# Schematic_Devices.net
KiCad netlist of a schematic drawn in Altium Designer
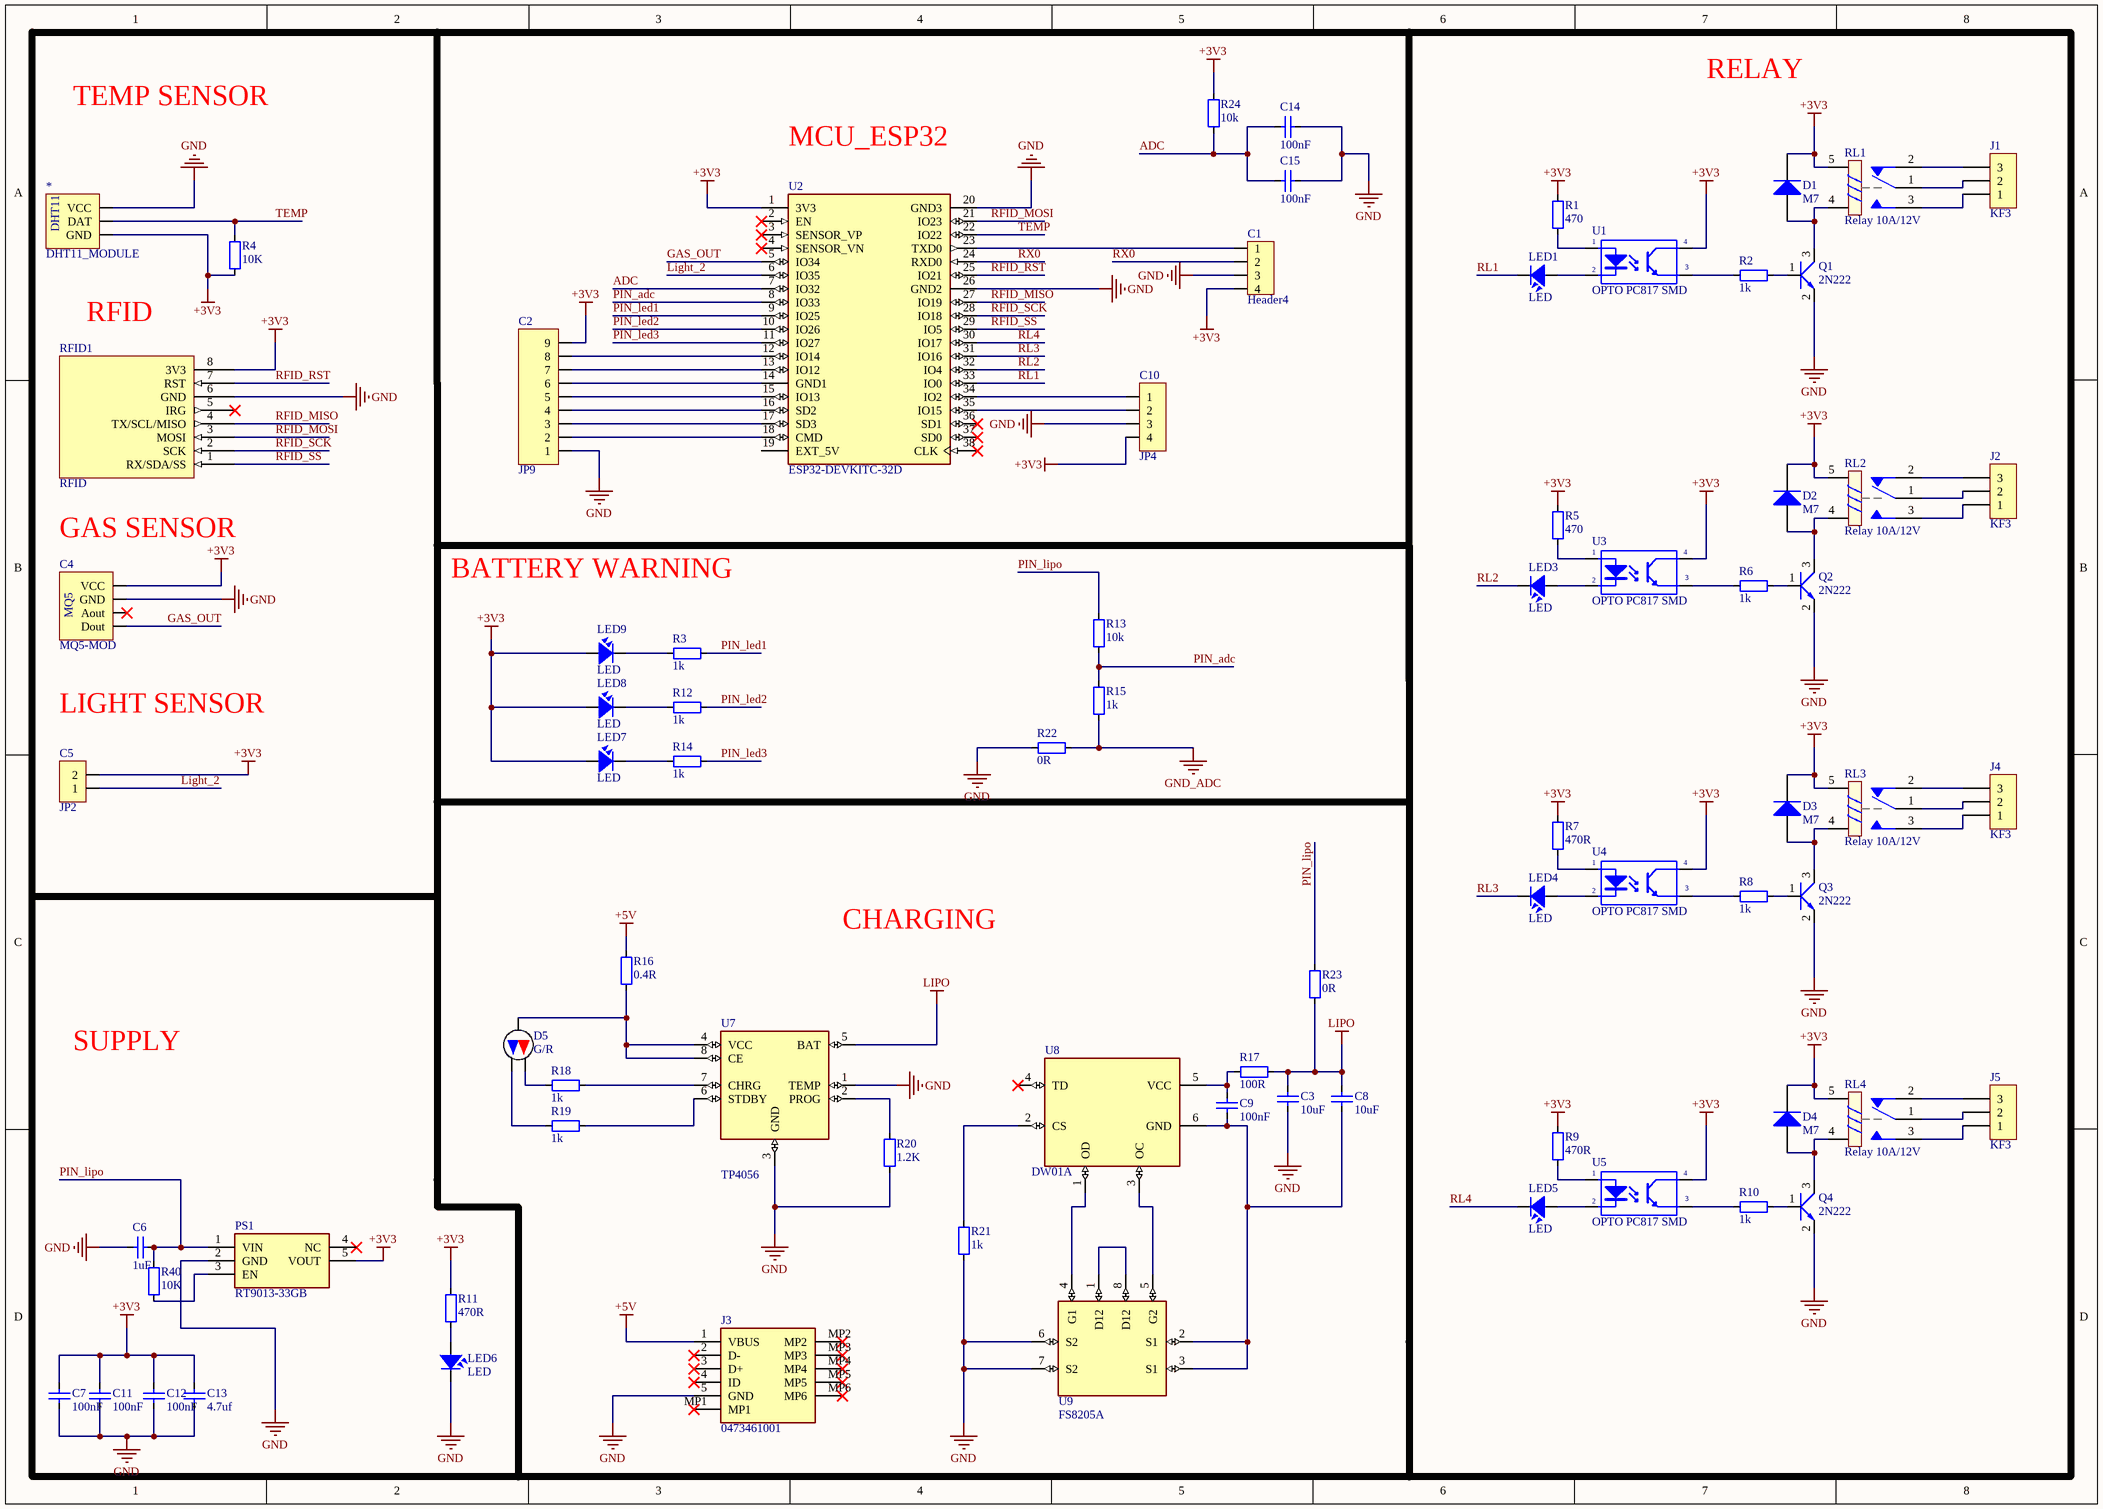
[diagram p0: Schematic_Devices.SchDoc]

(export (version "E")
  (design (tool "Eeschema 10.0.6"))
  (components
    (comp (ref "*")
      (value "DHT11_MODULE")
      (footprint "DHT11_MODULE")
      (libsource (lib "My Library") (part "DHT11_MODULE"))
    )
    (comp (ref "C1")
      (value "Header4")
      (footprint "HDR4")
      (description "Header IDC, 4 x 1 Pin Vertical 2.54mm Pitch (Non-Boxed, Male)")
      (fields
        (field (name "MANUFACTURER") "Würth Elektronik eiSos GmbH")
        (field (name "PARTNO") "613002143121")
        (field (name "CREATED BY") "Karrer Zheng")
      )
      (libsource (lib "My Library") (part "Header4"))
    )
    (comp (ref "C2")
      (value "JP9")
      (footprint "JP9-C1T")
      (description "WR-PHD 2.54 mm Angled Socket Header")
      (fields
        (field (name "MANUFACTURER") "Würth Elektronik eiSos GmbH")
        (field (name "PARTNO") "613009143121")
        (field (name "CREATED BY") "Karrer Zheng")
      )
      (libsource (lib "My Library") (part "JP9"))
    )
    (comp (ref "C3")
      (value "10uF")
      (footprint "CAP_0805")
      (description "Capacitor")
      (fields (field (name "PUBLISHER") "Altium Limited"))
      (libsource (lib "My Library") (part "CapSMD"))
    )
    (comp (ref "C4")
      (value "MQ5-MOD")
      (footprint "JP4-C1T")
      (fields
        (field (name "MANUFACTURER") "Würth Elektronik eiSos GmbH")
        (field (name "PARTNO") "613004143121")
        (field (name "CREATED BY") "Karrer Zheng")
      )
      (libsource (lib "My Library") (part "MQ5-MOD"))
    )
    (comp (ref "C5")
      (value "JP2")
      (footprint "JP2-C1T")
      (description "WR-PHD 2.54 mm Angled Socket Header")
      (fields
        (field (name "MANUFACTURER") "Würth Elektronik eiSos GmbH")
        (field (name "PARTNO") "613002143121")
        (field (name "CREATED BY") "Karrer Zheng")
      )
      (libsource (lib "My Library") (part "JP2"))
    )
    (comp (ref "C6")
      (value "1uF")
      (footprint "CAP_0805")
      (description "Capacitor")
      (fields (field (name "PUBLISHER") "Altium Limited"))
      (libsource (lib "My Library") (part "CapSMD"))
    )
    (comp (ref "C7")
      (value "100nF")
      (footprint "CAP_0805")
      (description "Capacitor")
      (fields (field (name "PUBLISHER") "Altium Limited"))
      (libsource (lib "My Library") (part "CapSMD"))
    )
    (comp (ref "C8")
      (value "10uF")
      (footprint "CAP_0805")
      (description "Capacitor")
      (fields (field (name "PUBLISHER") "Altium Limited"))
      (libsource (lib "My Library") (part "CapSMD"))
    )
    (comp (ref "C9")
      (value "100nF")
      (footprint "CAP_0805")
      (description "Capacitor")
      (fields (field (name "PUBLISHER") "Altium Limited"))
      (libsource (lib "My Library") (part "CapSMD"))
    )
    (comp (ref "C10")
      (value "JP4")
      (footprint "JP4-C1T")
      (description "WR-PHD 2.54 mm Angled Socket Header")
      (fields
        (field (name "MANUFACTURER") "Würth Elektronik eiSos GmbH")
        (field (name "PARTNO") "613004143121")
        (field (name "CREATED BY") "Karrer Zheng")
      )
      (libsource (lib "My Library") (part "JP4"))
    )
    (comp (ref "C11")
      (value "100nF")
      (footprint "CAP_0805")
      (description "Capacitor")
      (fields (field (name "PUBLISHER") "Altium Limited"))
      (libsource (lib "My Library") (part "CapSMD"))
    )
    (comp (ref "C12")
      (value "100nF")
      (footprint "CAP_0805")
      (description "Capacitor")
      (fields (field (name "PUBLISHER") "Altium Limited"))
      (libsource (lib "My Library") (part "CapSMD"))
    )
    (comp (ref "C13")
      (value "4.7uf")
      (footprint "CAP_0805")
      (description "Capacitor")
      (fields (field (name "PUBLISHER") "Altium Limited"))
      (libsource (lib "My Library") (part "CapSMD"))
    )
    (comp (ref "C14")
      (value "100nF")
      (footprint "CAP_0805")
      (description "Capacitor")
      (fields (field (name "PUBLISHER") "Altium Limited"))
      (libsource (lib "My Library") (part "CapSMD"))
    )
    (comp (ref "C15")
      (value "100nF")
      (footprint "CAP_0805")
      (description "Capacitor")
      (fields (field (name "PUBLISHER") "Altium Limited"))
      (libsource (lib "My Library") (part "CapSMD"))
    )
    (comp (ref "D1")
      (value "M7")
      (footprint "DO-214AC(SMA)")
      (description "Dán")
      (libsource (lib "Altium_Lib_by_KhueNguyenCreator") (part "Diode M7 ( 4007 )"))
    )
    (comp (ref "D2")
      (value "M7")
      (footprint "DO-214AC(SMA)")
      (description "Dán")
      (libsource (lib "Altium_Lib_by_KhueNguyenCreator") (part "Diode M7 ( 4007 )"))
    )
    (comp (ref "D3")
      (value "M7")
      (footprint "DO-214AC(SMA)")
      (description "Dán")
      (libsource (lib "Altium_Lib_by_KhueNguyenCreator") (part "Diode M7 ( 4007 )"))
    )
    (comp (ref "D4")
      (value "M7")
      (footprint "DO-214AC(SMA)")
      (description "Dán")
      (libsource (lib "Altium_Lib_by_KhueNguyenCreator") (part "Diode M7 ( 4007 )"))
    )
    (comp (ref "D5")
      (value "G/R")
      (footprint "LED_3MM_DUAL RA")
      (description "LED BLUE/RED DIFFUSED T-1 T/H 3MM")
      (fields (field (name "MFR") "SunLED") (field (name "MPN") "XLMDKCBD34M"))
      (libsource (lib "BYTECH_HW_LIB_2019 (1)") (part "LED_3MM_RA"))
    )
    (comp (ref "J1")
      (value "KF3")
      (footprint "KF3-5.08")
      (fields
        (field (name "MANUFACTURER") "Würth Elektronik eiSos GmbH")
        (field (name "PARTNO") "691103110003")
        (field (name "CREATED BY") "Karrer Zheng")
      )
      (libsource (lib "My Library") (part "KF3"))
    )
    (comp (ref "J2")
      (value "KF3")
      (footprint "KF3-5.08")
      (fields
        (field (name "MANUFACTURER") "Würth Elektronik eiSos GmbH")
        (field (name "PARTNO") "691103110003")
        (field (name "CREATED BY") "Karrer Zheng")
      )
      (libsource (lib "My Library") (part "KF3"))
    )
    (comp (ref "J3")
      (value "0473461001")
      (footprint "USB-M1")
      (description "Connector")
      (libsource (lib "*") (part "0473461001"))
    )
    (comp (ref "J4")
      (value "KF3")
      (footprint "KF3-5.08")
      (fields
        (field (name "MANUFACTURER") "Würth Elektronik eiSos GmbH")
        (field (name "PARTNO") "691103110003")
        (field (name "CREATED BY") "Karrer Zheng")
      )
      (libsource (lib "My Library") (part "KF3"))
    )
    (comp (ref "J5")
      (value "KF3")
      (footprint "KF3-5.08")
      (fields
        (field (name "MANUFACTURER") "Würth Elektronik eiSos GmbH")
        (field (name "PARTNO") "691103110003")
        (field (name "CREATED BY") "Karrer Zheng")
      )
      (libsource (lib "My Library") (part "KF3"))
    )
    (comp (ref "LED1")
      (value "LED")
      (footprint "LED-0805-Red")
      (description "LED Single colour Green and Red")
      (libsource (lib "My Library") (part "LED"))
    )
    (comp (ref "LED3")
      (value "LED")
      (footprint "LED-0805-Red")
      (description "LED Single colour Green and Red")
      (libsource (lib "My Library") (part "LED"))
    )
    (comp (ref "LED4")
      (value "LED")
      (footprint "LED-0805-Red")
      (description "LED Single colour Green and Red")
      (libsource (lib "My Library") (part "LED"))
    )
    (comp (ref "LED5")
      (value "LED")
      (footprint "LED-0805-Red")
      (description "LED Single colour Green and Red")
      (libsource (lib "My Library") (part "LED"))
    )
    (comp (ref "LED6")
      (value "LED")
      (footprint "LED-0805-Blue")
      (description "LED Single colour Green and Red")
      (libsource (lib "My Library") (part "LED"))
    )
    (comp (ref "LED7")
      (value "LED")
      (footprint "LED-0805-Orange")
      (description "LED Single colour Green and Red")
      (libsource (lib "My Library") (part "LED"))
    )
    (comp (ref "LED8")
      (value "LED")
      (footprint "LED-0805-Orange")
      (description "LED Single colour Green and Red")
      (libsource (lib "My Library") (part "LED"))
    )
    (comp (ref "LED9")
      (value "LED")
      (footprint "LED-0805-Blue")
      (description "LED Single colour Green and Red")
      (libsource (lib "My Library") (part "LED"))
    )
    (comp (ref "PS1")
      (value "RT9013-33GB")
      (footprint "SamacSys:SOT94P279X130-5N")
      (description "Power Supply")
      (libsource (lib "*") (part "RT9013-33GB"))
    )
    (comp (ref "Q1")
      (value "2N222")
      (footprint "SOT23D")
      (description "NPN 600mW, ECB")
      (libsource (lib "My Library") (part "2N222"))
    )
    (comp (ref "Q2")
      (value "2N222")
      (footprint "SOT23D")
      (description "NPN 600mW, ECB")
      (libsource (lib "My Library") (part "2N222"))
    )
    (comp (ref "Q3")
      (value "2N222")
      (footprint "SOT23D")
      (description "NPN 600mW, ECB")
      (libsource (lib "My Library") (part "2N222"))
    )
    (comp (ref "Q4")
      (value "2N222")
      (footprint "SOT23D")
      (description "NPN 600mW, ECB")
      (libsource (lib "My Library") (part "2N222"))
    )
    (comp (ref "R1")
      (value "470")
      (footprint "RES-SMD-0805")
      (description "Resistor")
      (fields
        (field (name "MANUFACTURER") "Generic Components")
        (field (name "PUBLISHER") "Altium Hobart Technology Centre")
      )
      (libsource (lib "My Library") (part "Resistor - SMD"))
    )
    (comp (ref "R2")
      (value "1k")
      (footprint "RES-SMD-0805")
      (description "Resistor")
      (fields
        (field (name "MANUFACTURER") "Generic Components")
        (field (name "PUBLISHER") "Altium Hobart Technology Centre")
      )
      (libsource (lib "My Library") (part "Resistor - SMD"))
    )
    (comp (ref "R3")
      (value "1k")
      (footprint "RES-SMD-0805")
      (description "Resistor")
      (fields
        (field (name "MANUFACTURER") "Generic Components")
        (field (name "PUBLISHER") "Altium Hobart Technology Centre")
      )
      (libsource (lib "My Library") (part "Resistor - SMD"))
    )
    (comp (ref "R4")
      (value "10K")
      (footprint "RES-SMD-0805")
      (description "Resistor")
      (fields
        (field (name "MANUFACTURER") "Generic Components")
        (field (name "PUBLISHER") "Altium Hobart Technology Centre")
      )
      (libsource (lib "My Library") (part "Resistor - SMD"))
    )
    (comp (ref "R5")
      (value "470")
      (footprint "RES-SMD-0805")
      (description "Resistor")
      (fields
        (field (name "MANUFACTURER") "Generic Components")
        (field (name "PUBLISHER") "Altium Hobart Technology Centre")
      )
      (libsource (lib "My Library") (part "Resistor - SMD"))
    )
    (comp (ref "R6")
      (value "1k")
      (footprint "RES-SMD-0805")
      (description "Resistor")
      (fields
        (field (name "MANUFACTURER") "Generic Components")
        (field (name "PUBLISHER") "Altium Hobart Technology Centre")
      )
      (libsource (lib "My Library") (part "Resistor - SMD"))
    )
    (comp (ref "R7")
      (value "470R")
      (footprint "RES-SMD-0805")
      (description "Resistor")
      (fields
        (field (name "MANUFACTURER") "Generic Components")
        (field (name "PUBLISHER") "Altium Hobart Technology Centre")
      )
      (libsource (lib "My Library") (part "Resistor - SMD"))
    )
    (comp (ref "R8")
      (value "1k")
      (footprint "RES-SMD-0805")
      (description "Resistor")
      (fields
        (field (name "MANUFACTURER") "Generic Components")
        (field (name "PUBLISHER") "Altium Hobart Technology Centre")
      )
      (libsource (lib "My Library") (part "Resistor - SMD"))
    )
    (comp (ref "R9")
      (value "470R")
      (footprint "RES-SMD-0805")
      (description "Resistor")
      (fields
        (field (name "MANUFACTURER") "Generic Components")
        (field (name "PUBLISHER") "Altium Hobart Technology Centre")
      )
      (libsource (lib "My Library") (part "Resistor - SMD"))
    )
    (comp (ref "R10")
      (value "1k")
      (footprint "RES-SMD-0805")
      (description "Resistor")
      (fields
        (field (name "MANUFACTURER") "Generic Components")
        (field (name "PUBLISHER") "Altium Hobart Technology Centre")
      )
      (libsource (lib "My Library") (part "Resistor - SMD"))
    )
    (comp (ref "R11")
      (value "470R")
      (footprint "RES-SMD-0805")
      (description "Resistor")
      (fields
        (field (name "MANUFACTURER") "Generic Components")
        (field (name "PUBLISHER") "Altium Hobart Technology Centre")
      )
      (libsource (lib "My Library") (part "Resistor - SMD"))
    )
    (comp (ref "R12")
      (value "1k")
      (footprint "RES-SMD-0805")
      (description "Resistor")
      (fields
        (field (name "MANUFACTURER") "Generic Components")
        (field (name "PUBLISHER") "Altium Hobart Technology Centre")
      )
      (libsource (lib "My Library") (part "Resistor - SMD"))
    )
    (comp (ref "R13")
      (value "10k")
      (footprint "RES-SMD-0805")
      (description "Resistor")
      (fields
        (field (name "MANUFACTURER") "Generic Components")
        (field (name "PUBLISHER") "Altium Hobart Technology Centre")
      )
      (libsource (lib "My Library") (part "Resistor - SMD"))
    )
    (comp (ref "R14")
      (value "1k")
      (footprint "RES-SMD-0805")
      (description "Resistor")
      (fields
        (field (name "MANUFACTURER") "Generic Components")
        (field (name "PUBLISHER") "Altium Hobart Technology Centre")
      )
      (libsource (lib "My Library") (part "Resistor - SMD"))
    )
    (comp (ref "R15")
      (value "1k")
      (footprint "RES-SMD-0805")
      (description "Resistor")
      (fields
        (field (name "MANUFACTURER") "Generic Components")
        (field (name "PUBLISHER") "Altium Hobart Technology Centre")
      )
      (libsource (lib "My Library") (part "Resistor - SMD"))
    )
    (comp (ref "R16")
      (value "0.4R")
      (footprint "RES-SMD-0805")
      (description "Resistor")
      (fields
        (field (name "MANUFACTURER") "Generic Components")
        (field (name "PUBLISHER") "Altium Hobart Technology Centre")
      )
      (libsource (lib "My Library") (part "Resistor - SMD"))
    )
    (comp (ref "R17")
      (value "100R")
      (footprint "RES-SMD-0805")
      (description "Resistor")
      (fields
        (field (name "MANUFACTURER") "Generic Components")
        (field (name "PUBLISHER") "Altium Hobart Technology Centre")
      )
      (libsource (lib "My Library") (part "Resistor - SMD"))
    )
    (comp (ref "R18")
      (value "1k")
      (footprint "RES-SMD-0805")
      (description "Resistor")
      (fields
        (field (name "MANUFACTURER") "Generic Components")
        (field (name "PUBLISHER") "Altium Hobart Technology Centre")
      )
      (libsource (lib "My Library") (part "Resistor - SMD"))
    )
    (comp (ref "R19")
      (value "1k")
      (footprint "RES-SMD-0805")
      (description "Resistor")
      (fields
        (field (name "MANUFACTURER") "Generic Components")
        (field (name "PUBLISHER") "Altium Hobart Technology Centre")
      )
      (libsource (lib "My Library") (part "Resistor - SMD"))
    )
    (comp (ref "R20")
      (value "1.2K")
      (footprint "RES-SMD-0805")
      (description "Resistor")
      (fields
        (field (name "MANUFACTURER") "Generic Components")
        (field (name "PUBLISHER") "Altium Hobart Technology Centre")
      )
      (libsource (lib "My Library") (part "Resistor - SMD"))
    )
    (comp (ref "R21")
      (value "1k")
      (footprint "RES-SMD-0805")
      (description "Resistor")
      (fields
        (field (name "MANUFACTURER") "Generic Components")
        (field (name "PUBLISHER") "Altium Hobart Technology Centre")
      )
      (libsource (lib "My Library") (part "Resistor - SMD"))
    )
    (comp (ref "R22")
      (value "0R")
      (footprint "RES-SMD-0805")
      (description "Resistor")
      (fields
        (field (name "MANUFACTURER") "Generic Components")
        (field (name "PUBLISHER") "Altium Hobart Technology Centre")
      )
      (libsource (lib "My Library") (part "Resistor - SMD"))
    )
    (comp (ref "R23")
      (value "0R")
      (footprint "RES-SMD-0805")
      (description "Resistor")
      (fields
        (field (name "MANUFACTURER") "Generic Components")
        (field (name "PUBLISHER") "Altium Hobart Technology Centre")
      )
      (libsource (lib "My Library") (part "Resistor - SMD"))
    )
    (comp (ref "R24")
      (value "10k")
      (footprint "RES-SMD-0805")
      (description "Resistor")
      (fields
        (field (name "MANUFACTURER") "Generic Components")
        (field (name "PUBLISHER") "Altium Hobart Technology Centre")
      )
      (libsource (lib "My Library") (part "Resistor - SMD"))
    )
    (comp (ref "R40")
      (value "10K")
      (footprint "RES-SMD-0805")
      (description "Resistor")
      (fields
        (field (name "MANUFACTURER") "Generic Components")
        (field (name "PUBLISHER") "Altium Hobart Technology Centre")
      )
      (libsource (lib "My Library") (part "Resistor - SMD"))
    )
    (comp (ref "RFID1")
      (value "RFID")
      (footprint "RFID RC522")
      (libsource (lib "My Library") (part "RFID RC522"))
    )
    (comp (ref "RL1")
      (value "Relay 10A/12V")
      (footprint "RELAY5PIN-10A")
      (description "Relay SPDT,10A - 12VDC 5 Pin")
      (libsource (lib "My Library") (part "Relay 5"))
    )
    (comp (ref "RL2")
      (value "Relay 10A/12V")
      (footprint "RELAY5PIN-10A")
      (description "Relay SPDT,10A - 12VDC 5 Pin")
      (libsource (lib "My Library") (part "Relay 5"))
    )
    (comp (ref "RL3")
      (value "Relay 10A/12V")
      (footprint "RELAY5PIN-10A")
      (description "Relay SPDT,10A - 12VDC 5 Pin")
      (libsource (lib "My Library") (part "Relay 5"))
    )
    (comp (ref "RL4")
      (value "Relay 10A/12V")
      (footprint "RELAY5PIN-10A")
      (description "Relay SPDT,10A - 12VDC 5 Pin")
      (libsource (lib "My Library") (part "Relay 5"))
    )
    (comp (ref "U1")
      (value "OPTO PC817 SMD")
      (footprint "OPTO_SMD")
      (description "Single Opto")
      (libsource (lib "Altium_Lib_by_KhueNguyenCreator") (part "OPTO PC817 SMD"))
    )
    (comp (ref "U2")
      (value "ESP32-DEVKITC-32D")
      (footprint "MODULE_ESP32-DEVKITC-32D")
      (description "EVAL BOARD FOR ESP-WROOM-32")
      (fields (field (name "MF") "Espressif Systems"))
      (libsource (lib "My Library") (part "ESP32-DEVKITC-32D"))
    )
    (comp (ref "U3")
      (value "OPTO PC817 SMD")
      (footprint "OPTO_SMD")
      (description "Single Opto")
      (libsource (lib "Altium_Lib_by_KhueNguyenCreator") (part "OPTO PC817 SMD"))
    )
    (comp (ref "U4")
      (value "OPTO PC817 SMD")
      (footprint "OPTO_SMD")
      (description "Single Opto")
      (libsource (lib "Altium_Lib_by_KhueNguyenCreator") (part "OPTO PC817 SMD"))
    )
    (comp (ref "U5")
      (value "OPTO PC817 SMD")
      (footprint "OPTO_SMD")
      (description "Single Opto")
      (libsource (lib "Altium_Lib_by_KhueNguyenCreator") (part "OPTO PC817 SMD"))
    )
    (comp (ref "U7")
      (value "TP4056")
      (footprint "TP4056")
      (description "Complete single cell Li-Ion battery with a constant current / constant voltage linear charger")
      (libsource (lib "My Library") (part "TP4056"))
    )
    (comp (ref "U8")
      (value "DW01A")
      (footprint "SOT23-6")
      (description "One Cell Lithium-ion/Polymer Battery Protection IC")
      (libsource (lib "My Library") (part "DW01A"))
    )
    (comp (ref "U9") (value "FS8205A") (footprint "FS8205A") (libsource (lib "My Library") (part "FS8205A")))
  )
  (nets
    (net (code "1") (name "+3V3") (class "Default")
      (node (ref "*") (pin "1") (pinfunction "GND_1") (pintype "passive"))
      (node (ref "C1") (pin "4") (pinfunction "4_4") (pintype "passive"))
      (node (ref "C10") (pin "4") (pinfunction "4_4") (pintype "passive"))
      (node (ref "C11") (pin "2") (pinfunction "2_2") (pintype "passive"))
      (node (ref "C12") (pin "2") (pinfunction "2_2") (pintype "passive"))
      (node (ref "C13") (pin "2") (pinfunction "2_2") (pintype "passive"))
      (node (ref "C2") (pin "9") (pinfunction "9_9") (pintype "passive"))
      (node (ref "C4") (pin "4") (pinfunction "VCC_4") (pintype "passive"))
      (node (ref "C5") (pin "2") (pinfunction "2_2") (pintype "passive"))
      (node (ref "C7") (pin "2") (pinfunction "2_2") (pintype "passive"))
      (node (ref "D1") (pin "2") (pinfunction "K_2") (pintype "passive"))
      (node (ref "D2") (pin "2") (pinfunction "K_2") (pintype "passive"))
      (node (ref "D3") (pin "2") (pinfunction "K_2") (pintype "passive"))
      (node (ref "D4") (pin "2") (pinfunction "K_2") (pintype "passive"))
      (node (ref "LED7") (pin "1") (pinfunction "1_1") (pintype "passive"))
      (node (ref "LED8") (pin "1") (pinfunction "1_1") (pintype "passive"))
      (node (ref "LED9") (pin "1") (pinfunction "1_1") (pintype "passive"))
      (node (ref "PS1") (pin "5") (pinfunction "VOUT_5") (pintype "passive"))
      (node (ref "R1") (pin "1") (pinfunction "1_1") (pintype "passive"))
      (node (ref "R11") (pin "1") (pinfunction "1_1") (pintype "passive"))
      (node (ref "R24") (pin "2") (pinfunction "2_2") (pintype "passive"))
      (node (ref "R4") (pin "1") (pinfunction "1_1") (pintype "passive"))
      (node (ref "R5") (pin "1") (pinfunction "1_1") (pintype "passive"))
      (node (ref "R7") (pin "1") (pinfunction "1_1") (pintype "passive"))
      (node (ref "R9") (pin "1") (pinfunction "1_1") (pintype "passive"))
      (node (ref "RFID1") (pin "8") (pinfunction "3V3_8") (pintype "power_in"))
      (node (ref "RL1") (pin "5") (pinfunction "5_5") (pintype "passive"))
      (node (ref "RL2") (pin "5") (pinfunction "5_5") (pintype "passive"))
      (node (ref "RL3") (pin "5") (pinfunction "5_5") (pintype "passive"))
      (node (ref "RL4") (pin "5") (pinfunction "5_5") (pintype "passive"))
      (node (ref "U1") (pin "4") (pinfunction "C_4") (pintype "passive"))
      (node (ref "U2") (pin "1") (pinfunction "3V3_1") (pintype "power_in"))
      (node (ref "U3") (pin "4") (pinfunction "C_4") (pintype "passive"))
      (node (ref "U4") (pin "4") (pinfunction "C_4") (pintype "passive"))
      (node (ref "U5") (pin "4") (pinfunction "C_4") (pintype "passive"))
    )
    (net (code "2") (name "+5V") (class "Default")
      (node (ref "J3") (pin "1") (pinfunction "VBUS_1") (pintype "passive"))
      (node (ref "R16") (pin "2") (pinfunction "2_2") (pintype "passive"))
    )
    (net (code "3") (name "/ADC") (class "Default")
      (node (ref "C14") (pin "1") (pinfunction "1_1") (pintype "passive"))
      (node (ref "C15") (pin "1") (pinfunction "1_1") (pintype "passive"))
      (node (ref "R24") (pin "1") (pinfunction "1_1") (pintype "passive"))
      (node (ref "U2") (pin "7") (pinfunction "IO32_7") (pintype "bidirectional"))
    )
    (net (code "4") (name "/GAS_OUT") (class "Default")
      (node (ref "C4") (pin "1") (pinfunction "Dout_1") (pintype "passive"))
      (node (ref "U2") (pin "5") (pinfunction "IO34_5") (pintype "bidirectional"))
    )
    (net (code "5") (name "/Light_2") (class "Default")
      (node (ref "C5") (pin "1") (pinfunction "1_1") (pintype "passive"))
      (node (ref "U2") (pin "6") (pinfunction "IO35_6") (pintype "bidirectional"))
    )
    (net (code "6") (name "/PIN_adc") (class "Default")
      (node (ref "R13") (pin "1") (pinfunction "1_1") (pintype "passive"))
      (node (ref "R15") (pin "2") (pinfunction "2_2") (pintype "passive"))
      (node (ref "U2") (pin "8") (pinfunction "IO33_8") (pintype "bidirectional"))
    )
    (net (code "7") (name "/PIN_led1") (class "Default")
      (node (ref "R3") (pin "2") (pinfunction "2_2") (pintype "passive"))
      (node (ref "U2") (pin "9") (pinfunction "IO25_9") (pintype "bidirectional"))
    )
    (net (code "8") (name "/PIN_led2") (class "Default")
      (node (ref "R12") (pin "2") (pinfunction "2_2") (pintype "passive"))
      (node (ref "U2") (pin "10") (pinfunction "IO26_10") (pintype "bidirectional"))
    )
    (net (code "9") (name "/PIN_led3") (class "Default")
      (node (ref "R14") (pin "2") (pinfunction "2_2") (pintype "passive"))
      (node (ref "U2") (pin "11") (pinfunction "IO27_11") (pintype "bidirectional"))
    )
    (net (code "10") (name "/PIN_lipo") (class "Default")
      (node (ref "C6") (pin "2") (pinfunction "2_2") (pintype "passive"))
      (node (ref "PS1") (pin "1") (pinfunction "VIN_1") (pintype "passive"))
      (node (ref "R13") (pin "2") (pinfunction "2_2") (pintype "passive"))
      (node (ref "R23") (pin "1") (pinfunction "1_1") (pintype "passive"))
      (node (ref "R40") (pin "2") (pinfunction "2_2") (pintype "passive"))
    )
    (net (code "11") (name "/RFID_MISO") (class "Default")
      (node (ref "RFID1") (pin "4") (pinfunction "TX/SCL/MISO_4") (pintype "output"))
      (node (ref "U2") (pin "27") (pinfunction "IO19_27") (pintype "bidirectional"))
    )
    (net (code "12") (name "/RFID_MOSI") (class "Default")
      (node (ref "RFID1") (pin "3") (pinfunction "MOSI_3") (pintype "input"))
      (node (ref "U2") (pin "21") (pinfunction "IO23_21") (pintype "bidirectional"))
    )
    (net (code "13") (name "/RFID_RST") (class "Default")
      (node (ref "RFID1") (pin "7") (pinfunction "RST_7") (pintype "input"))
      (node (ref "U2") (pin "25") (pinfunction "IO21_25") (pintype "bidirectional"))
    )
    (net (code "14") (name "/RFID_SCK") (class "Default")
      (node (ref "RFID1") (pin "2") (pinfunction "SCK_2") (pintype "input"))
      (node (ref "U2") (pin "28") (pinfunction "IO18_28") (pintype "bidirectional"))
    )
    (net (code "15") (name "/RFID_SS") (class "Default")
      (node (ref "RFID1") (pin "1") (pinfunction "RX/SDA/SS_1") (pintype "input"))
      (node (ref "U2") (pin "29") (pinfunction "IO5_29") (pintype "bidirectional"))
    )
    (net (code "16") (name "/RL1") (class "Default")
      (node (ref "LED1") (pin "2") (pinfunction "2_2") (pintype "passive"))
      (node (ref "U2") (pin "33") (pinfunction "IO0_33") (pintype "bidirectional"))
    )
    (net (code "17") (name "/RL2") (class "Default")
      (node (ref "LED3") (pin "2") (pinfunction "2_2") (pintype "passive"))
      (node (ref "U2") (pin "32") (pinfunction "IO4_32") (pintype "bidirectional"))
    )
    (net (code "18") (name "/RL3") (class "Default")
      (node (ref "LED4") (pin "2") (pinfunction "2_2") (pintype "passive"))
      (node (ref "U2") (pin "31") (pinfunction "IO16_31") (pintype "bidirectional"))
    )
    (net (code "19") (name "/RL4") (class "Default")
      (node (ref "LED5") (pin "2") (pinfunction "2_2") (pintype "passive"))
      (node (ref "U2") (pin "30") (pinfunction "IO17_30") (pintype "bidirectional"))
    )
    (net (code "20") (name "/RX0") (class "Default")
      (node (ref "C1") (pin "2") (pinfunction "2_2") (pintype "passive"))
      (node (ref "U2") (pin "24") (pinfunction "RXD0_24") (pintype "input"))
    )
    (net (code "21") (name "/TEMP") (class "Default")
      (node (ref "*") (pin "2") (pinfunction "DAT_2") (pintype "passive"))
      (node (ref "R4") (pin "2") (pinfunction "2_2") (pintype "passive"))
      (node (ref "U2") (pin "22") (pinfunction "IO22_22") (pintype "bidirectional"))
    )
    (net (code "22") (name "GND") (class "Default")
      (node (ref "*") (pin "3") (pinfunction "VCC_3") (pintype "passive"))
      (node (ref "C1") (pin "3") (pinfunction "3_3") (pintype "passive"))
      (node (ref "C10") (pin "3") (pinfunction "3_3") (pintype "passive"))
      (node (ref "C11") (pin "1") (pinfunction "1_1") (pintype "passive"))
      (node (ref "C12") (pin "1") (pinfunction "1_1") (pintype "passive"))
      (node (ref "C13") (pin "1") (pinfunction "1_1") (pintype "passive"))
      (node (ref "C14") (pin "2") (pinfunction "2_2") (pintype "passive"))
      (node (ref "C15") (pin "2") (pinfunction "2_2") (pintype "passive"))
      (node (ref "C2") (pin "1") (pinfunction "1_1") (pintype "passive"))
      (node (ref "C3") (pin "1") (pinfunction "1_1") (pintype "passive"))
      (node (ref "C4") (pin "3") (pinfunction "GND_3") (pintype "passive"))
      (node (ref "C6") (pin "1") (pinfunction "1_1") (pintype "passive"))
      (node (ref "C7") (pin "1") (pinfunction "1_1") (pintype "passive"))
      (node (ref "J3") (pin "5") (pinfunction "GND_5") (pintype "passive"))
      (node (ref "LED6") (pin "2") (pinfunction "2_2") (pintype "passive"))
      (node (ref "PS1") (pin "2") (pinfunction "GND_2") (pintype "passive"))
      (node (ref "Q1") (pin "2") (pinfunction "E_2") (pintype "passive"))
      (node (ref "Q2") (pin "2") (pinfunction "E_2") (pintype "passive"))
      (node (ref "Q3") (pin "2") (pinfunction "E_2") (pintype "passive"))
      (node (ref "Q4") (pin "2") (pinfunction "E_2") (pintype "passive"))
      (node (ref "R20") (pin "1") (pinfunction "1_1") (pintype "passive"))
      (node (ref "R21") (pin "1") (pinfunction "1_1") (pintype "passive"))
      (node (ref "R22") (pin "2") (pinfunction "2_2") (pintype "passive"))
      (node (ref "RFID1") (pin "6") (pinfunction "GND_6") (pintype "power_in"))
      (node (ref "U2") (pin "20") (pinfunction "GND3_20") (pintype "power_in"))
      (node (ref "U2") (pin "26") (pinfunction "GND2_26") (pintype "power_in"))
      (node (ref "U7") (pin "1") (pinfunction "TEMP_1") (pintype "bidirectional"))
      (node (ref "U7") (pin "3") (pinfunction "GND_3") (pintype "bidirectional"))
      (node (ref "U9") (pin "6") (pinfunction "S2_6") (pintype "bidirectional"))
      (node (ref "U9") (pin "7") (pinfunction "S2_7") (pintype "bidirectional"))
    )
    (net (code "23") (name "GND_ADC") (class "Default")
      (node (ref "R15") (pin "1") (pinfunction "1_1") (pintype "passive"))
      (node (ref "R22") (pin "1") (pinfunction "1_1") (pintype "passive"))
    )
    (net (code "24") (name "LIPO") (class "Default")
      (node (ref "C3") (pin "2") (pinfunction "2_2") (pintype "passive"))
      (node (ref "C8") (pin "2") (pinfunction "2_2") (pintype "passive"))
      (node (ref "R17") (pin "1") (pinfunction "1_1") (pintype "passive"))
      (node (ref "R23") (pin "2") (pinfunction "2_2") (pintype "passive"))
      (node (ref "U7") (pin "5") (pinfunction "BAT_5") (pintype "bidirectional"))
    )
    (net (code "25") (name "Net-(D1-A)") (class "Default")
      (node (ref "D1") (pin "1") (pinfunction "A_1") (pintype "passive"))
      (node (ref "Q1") (pin "3") (pinfunction "C_3") (pintype "passive"))
      (node (ref "RL1") (pin "4") (pinfunction "4_4") (pintype "passive"))
    )
    (net (code "26") (name "Net-(D2-A)") (class "Default")
      (node (ref "D2") (pin "1") (pinfunction "A_1") (pintype "passive"))
      (node (ref "Q2") (pin "3") (pinfunction "C_3") (pintype "passive"))
      (node (ref "RL2") (pin "4") (pinfunction "4_4") (pintype "passive"))
    )
    (net (code "27") (name "Net-(D3-A)") (class "Default")
      (node (ref "D3") (pin "1") (pinfunction "A_1") (pintype "passive"))
      (node (ref "Q3") (pin "3") (pinfunction "C_3") (pintype "passive"))
      (node (ref "RL3") (pin "4") (pinfunction "4_4") (pintype "passive"))
    )
    (net (code "28") (name "Net-(D4-A)") (class "Default")
      (node (ref "D4") (pin "1") (pinfunction "A_1") (pintype "passive"))
      (node (ref "Q4") (pin "3") (pinfunction "C_3") (pintype "passive"))
      (node (ref "RL4") (pin "4") (pinfunction "4_4") (pintype "passive"))
    )
    (net (code "29") (name "Net-(D5-A)") (class "Default")
      (node (ref "D5") (pin "2") (pinfunction "A_2") (pintype "passive"))
      (node (ref "R16") (pin "1") (pinfunction "1_1") (pintype "passive"))
      (node (ref "U7") (pin "4") (pinfunction "VCC_4") (pintype "bidirectional"))
      (node (ref "U7") (pin "8") (pinfunction "CE_8") (pintype "bidirectional"))
    )
    (net (code "30") (name "Net-(D5-KB)") (class "Default")
      (node (ref "D5") (pin "3") (pinfunction "KB_3") (pintype "passive"))
      (node (ref "R18") (pin "1") (pinfunction "1_1") (pintype "passive"))
    )
    (net (code "31") (name "Net-(D5-KR)") (class "Default")
      (node (ref "D5") (pin "1") (pinfunction "KR_1") (pintype "passive"))
      (node (ref "R19") (pin "1") (pinfunction "1_1") (pintype "passive"))
    )
    (net (code "32") (name "Net-(J1-Pad1)") (class "Default")
      (node (ref "J1") (pin "1") (pinfunction "1_1") (pintype "passive"))
      (node (ref "RL1") (pin "3") (pinfunction "3_3") (pintype "passive"))
    )
    (net (code "33") (name "Net-(J1-Pad2)") (class "Default")
      (node (ref "J1") (pin "2") (pinfunction "2_2") (pintype "passive"))
      (node (ref "RL1") (pin "1") (pinfunction "1_1") (pintype "passive"))
    )
    (net (code "34") (name "Net-(J1-Pad3)") (class "Default")
      (node (ref "J1") (pin "3") (pinfunction "3_3") (pintype "passive"))
      (node (ref "RL1") (pin "2") (pinfunction "2_2") (pintype "passive"))
    )
    (net (code "35") (name "Net-(J2-Pad1)") (class "Default")
      (node (ref "J2") (pin "1") (pinfunction "1_1") (pintype "passive"))
      (node (ref "RL2") (pin "3") (pinfunction "3_3") (pintype "passive"))
    )
    (net (code "36") (name "Net-(J2-Pad2)") (class "Default")
      (node (ref "J2") (pin "2") (pinfunction "2_2") (pintype "passive"))
      (node (ref "RL2") (pin "1") (pinfunction "1_1") (pintype "passive"))
    )
    (net (code "37") (name "Net-(J2-Pad3)") (class "Default")
      (node (ref "J2") (pin "3") (pinfunction "3_3") (pintype "passive"))
      (node (ref "RL2") (pin "2") (pinfunction "2_2") (pintype "passive"))
    )
    (net (code "38") (name "Net-(J4-Pad1)") (class "Default")
      (node (ref "J4") (pin "1") (pinfunction "1_1") (pintype "passive"))
      (node (ref "RL3") (pin "3") (pinfunction "3_3") (pintype "passive"))
    )
    (net (code "39") (name "Net-(J4-Pad2)") (class "Default")
      (node (ref "J4") (pin "2") (pinfunction "2_2") (pintype "passive"))
      (node (ref "RL3") (pin "1") (pinfunction "1_1") (pintype "passive"))
    )
    (net (code "40") (name "Net-(J4-Pad3)") (class "Default")
      (node (ref "J4") (pin "3") (pinfunction "3_3") (pintype "passive"))
      (node (ref "RL3") (pin "2") (pinfunction "2_2") (pintype "passive"))
    )
    (net (code "41") (name "Net-(J5-Pad1)") (class "Default")
      (node (ref "J5") (pin "1") (pinfunction "1_1") (pintype "passive"))
      (node (ref "RL4") (pin "3") (pinfunction "3_3") (pintype "passive"))
    )
    (net (code "42") (name "Net-(J5-Pad2)") (class "Default")
      (node (ref "J5") (pin "2") (pinfunction "2_2") (pintype "passive"))
      (node (ref "RL4") (pin "1") (pinfunction "1_1") (pintype "passive"))
    )
    (net (code "43") (name "Net-(J5-Pad3)") (class "Default")
      (node (ref "J5") (pin "3") (pinfunction "3_3") (pintype "passive"))
      (node (ref "RL4") (pin "2") (pinfunction "2_2") (pintype "passive"))
    )
    (net (code "44") (name "Net-(LED6-Pad1)") (class "Default")
      (node (ref "LED6") (pin "1") (pinfunction "1_1") (pintype "passive"))
      (node (ref "R11") (pin "2") (pinfunction "2_2") (pintype "passive"))
    )
    (net (code "45") (name "Net-(LED7-Pad2)") (class "Default")
      (node (ref "LED7") (pin "2") (pinfunction "2_2") (pintype "passive"))
      (node (ref "R14") (pin "1") (pinfunction "1_1") (pintype "passive"))
    )
    (net (code "46") (name "Net-(LED8-Pad2)") (class "Default")
      (node (ref "LED8") (pin "2") (pinfunction "2_2") (pintype "passive"))
      (node (ref "R12") (pin "1") (pinfunction "1_1") (pintype "passive"))
    )
    (net (code "47") (name "Net-(LED9-Pad2)") (class "Default")
      (node (ref "LED9") (pin "2") (pinfunction "2_2") (pintype "passive"))
      (node (ref "R3") (pin "1") (pinfunction "1_1") (pintype "passive"))
    )
    (net (code "48") (name "Net-(PS1-EN)") (class "Default")
      (node (ref "PS1") (pin "3") (pinfunction "EN_3") (pintype "passive"))
      (node (ref "R40") (pin "1") (pinfunction "1_1") (pintype "passive"))
    )
    (net (code "49") (name "Net-(Q1-B)") (class "Default")
      (node (ref "Q1") (pin "1") (pinfunction "B_1") (pintype "passive"))
      (node (ref "R2") (pin "2") (pinfunction "2_2") (pintype "passive"))
    )
    (net (code "50") (name "Net-(Q2-B)") (class "Default")
      (node (ref "Q2") (pin "1") (pinfunction "B_1") (pintype "passive"))
      (node (ref "R6") (pin "2") (pinfunction "2_2") (pintype "passive"))
    )
    (net (code "51") (name "Net-(Q3-B)") (class "Default")
      (node (ref "Q3") (pin "1") (pinfunction "B_1") (pintype "passive"))
      (node (ref "R8") (pin "2") (pinfunction "2_2") (pintype "passive"))
    )
    (net (code "52") (name "Net-(Q4-B)") (class "Default")
      (node (ref "Q4") (pin "1") (pinfunction "B_1") (pintype "passive"))
      (node (ref "R10") (pin "2") (pinfunction "2_2") (pintype "passive"))
    )
    (net (code "53") (name "Net-(U1-A)") (class "Default")
      (node (ref "R1") (pin "2") (pinfunction "2_2") (pintype "passive"))
      (node (ref "U1") (pin "1") (pinfunction "A_1") (pintype "passive"))
    )
    (net (code "54") (name "Net-(U1-E)") (class "Default")
      (node (ref "R2") (pin "1") (pinfunction "1_1") (pintype "passive"))
      (node (ref "U1") (pin "3") (pinfunction "E_3") (pintype "passive"))
    )
    (net (code "55") (name "Net-(U1-K)") (class "Default")
      (node (ref "LED1") (pin "1") (pinfunction "1_1") (pintype "passive"))
      (node (ref "U1") (pin "2") (pinfunction "K_2") (pintype "passive"))
    )
    (net (code "56") (name "Net-(U2-CMD)") (class "Default")
      (node (ref "C2") (pin "2") (pinfunction "2_2") (pintype "passive"))
      (node (ref "U2") (pin "18") (pinfunction "CMD_18") (pintype "bidirectional"))
    )
    (net (code "57") (name "Net-(U2-GND1)") (class "Default")
      (node (ref "C2") (pin "6") (pinfunction "6_6") (pintype "passive"))
      (node (ref "U2") (pin "14") (pinfunction "GND1_14") (pintype "power_in"))
    )
    (net (code "58") (name "Net-(U2-IO2)") (class "Default")
      (node (ref "C10") (pin "1") (pinfunction "1_1") (pintype "passive"))
      (node (ref "U2") (pin "34") (pinfunction "IO2_34") (pintype "bidirectional"))
    )
    (net (code "59") (name "Net-(U2-IO12)") (class "Default")
      (node (ref "C2") (pin "7") (pinfunction "7_7") (pintype "passive"))
      (node (ref "U2") (pin "13") (pinfunction "IO12_13") (pintype "bidirectional"))
    )
    (net (code "60") (name "Net-(U2-IO13)") (class "Default")
      (node (ref "C2") (pin "5") (pinfunction "5_5") (pintype "passive"))
      (node (ref "U2") (pin "15") (pinfunction "IO13_15") (pintype "bidirectional"))
    )
    (net (code "61") (name "Net-(U2-IO14)") (class "Default")
      (node (ref "C2") (pin "8") (pinfunction "8_8") (pintype "passive"))
      (node (ref "U2") (pin "12") (pinfunction "IO14_12") (pintype "bidirectional"))
    )
    (net (code "62") (name "Net-(U2-IO15)") (class "Default")
      (node (ref "C10") (pin "2") (pinfunction "2_2") (pintype "passive"))
      (node (ref "U2") (pin "35") (pinfunction "IO15_35") (pintype "bidirectional"))
    )
    (net (code "63") (name "Net-(U2-SD2)") (class "Default")
      (node (ref "C2") (pin "4") (pinfunction "4_4") (pintype "passive"))
      (node (ref "U2") (pin "16") (pinfunction "SD2_16") (pintype "bidirectional"))
    )
    (net (code "64") (name "Net-(U2-SD3)") (class "Default")
      (node (ref "C2") (pin "3") (pinfunction "3_3") (pintype "passive"))
      (node (ref "U2") (pin "17") (pinfunction "SD3_17") (pintype "bidirectional"))
    )
    (net (code "65") (name "Net-(U2-TXD0)") (class "Default")
      (node (ref "C1") (pin "1") (pinfunction "1_1") (pintype "passive"))
      (node (ref "U2") (pin "23") (pinfunction "TXD0_23") (pintype "output"))
    )
    (net (code "66") (name "Net-(U3-A)") (class "Default")
      (node (ref "R5") (pin "2") (pinfunction "2_2") (pintype "passive"))
      (node (ref "U3") (pin "1") (pinfunction "A_1") (pintype "passive"))
    )
    (net (code "67") (name "Net-(U3-E)") (class "Default")
      (node (ref "R6") (pin "1") (pinfunction "1_1") (pintype "passive"))
      (node (ref "U3") (pin "3") (pinfunction "E_3") (pintype "passive"))
    )
    (net (code "68") (name "Net-(U3-K)") (class "Default")
      (node (ref "LED3") (pin "1") (pinfunction "1_1") (pintype "passive"))
      (node (ref "U3") (pin "2") (pinfunction "K_2") (pintype "passive"))
    )
    (net (code "69") (name "Net-(U4-A)") (class "Default")
      (node (ref "R7") (pin "2") (pinfunction "2_2") (pintype "passive"))
      (node (ref "U4") (pin "1") (pinfunction "A_1") (pintype "passive"))
    )
    (net (code "70") (name "Net-(U4-E)") (class "Default")
      (node (ref "R8") (pin "1") (pinfunction "1_1") (pintype "passive"))
      (node (ref "U4") (pin "3") (pinfunction "E_3") (pintype "passive"))
    )
    (net (code "71") (name "Net-(U4-K)") (class "Default")
      (node (ref "LED4") (pin "1") (pinfunction "1_1") (pintype "passive"))
      (node (ref "U4") (pin "2") (pinfunction "K_2") (pintype "passive"))
    )
    (net (code "72") (name "Net-(U5-A)") (class "Default")
      (node (ref "R9") (pin "2") (pinfunction "2_2") (pintype "passive"))
      (node (ref "U5") (pin "1") (pinfunction "A_1") (pintype "passive"))
    )
    (net (code "73") (name "Net-(U5-E)") (class "Default")
      (node (ref "R10") (pin "1") (pinfunction "1_1") (pintype "passive"))
      (node (ref "U5") (pin "3") (pinfunction "E_3") (pintype "passive"))
    )
    (net (code "74") (name "Net-(U5-K)") (class "Default")
      (node (ref "LED5") (pin "1") (pinfunction "1_1") (pintype "passive"))
      (node (ref "U5") (pin "2") (pinfunction "K_2") (pintype "passive"))
    )
    (net (code "75") (name "Net-(U7-CHRG)") (class "Default")
      (node (ref "R18") (pin "2") (pinfunction "2_2") (pintype "passive"))
      (node (ref "U7") (pin "7") (pinfunction "CHRG_7") (pintype "bidirectional"))
    )
    (net (code "76") (name "Net-(U7-PROG)") (class "Default")
      (node (ref "R20") (pin "2") (pinfunction "2_2") (pintype "passive"))
      (node (ref "U7") (pin "2") (pinfunction "PROG_2") (pintype "bidirectional"))
    )
    (net (code "77") (name "Net-(U7-STDBY)") (class "Default")
      (node (ref "R19") (pin "2") (pinfunction "2_2") (pintype "passive"))
      (node (ref "U7") (pin "6") (pinfunction "STDBY_6") (pintype "bidirectional"))
    )
    (net (code "78") (name "Net-(U8-CS)") (class "Default")
      (node (ref "R21") (pin "2") (pinfunction "2_2") (pintype "passive"))
      (node (ref "U8") (pin "2") (pinfunction "CS_2") (pintype "bidirectional"))
    )
    (net (code "79") (name "Net-(U8-GND)") (class "Default")
      (node (ref "C8") (pin "1") (pinfunction "1_1") (pintype "passive"))
      (node (ref "C9") (pin "1") (pinfunction "1_1") (pintype "passive"))
      (node (ref "U8") (pin "6") (pinfunction "GND_6") (pintype "power_in"))
      (node (ref "U9") (pin "2") (pinfunction "S1_2") (pintype "bidirectional"))
      (node (ref "U9") (pin "3") (pinfunction "S1_3") (pintype "bidirectional"))
    )
    (net (code "80") (name "Net-(U8-OC)") (class "Default")
      (node (ref "U8") (pin "3") (pinfunction "OC_3") (pintype "bidirectional"))
      (node (ref "U9") (pin "5") (pinfunction "G2_5") (pintype "bidirectional"))
    )
    (net (code "81") (name "Net-(U8-OD)") (class "Default")
      (node (ref "U8") (pin "1") (pinfunction "OD_1") (pintype "bidirectional"))
      (node (ref "U9") (pin "4") (pinfunction "G1_4") (pintype "bidirectional"))
    )
    (net (code "82") (name "Net-(U8-VCC)") (class "Default")
      (node (ref "C9") (pin "2") (pinfunction "2_2") (pintype "passive"))
      (node (ref "R17") (pin "2") (pinfunction "2_2") (pintype "passive"))
      (node (ref "U8") (pin "5") (pinfunction "VCC_5") (pintype "power_in"))
    )
    (net (code "83") (name "Net-(U9-D12-Pad1)") (class "Default")
      (node (ref "U9") (pin "1") (pinfunction "D12_1") (pintype "bidirectional"))
      (node (ref "U9") (pin "8") (pinfunction "D12_8") (pintype "bidirectional"))
    )
    (net (code "84") (name "unconnected-(C4-Aout-Pad2)") (class "Default")
      (node (ref "C4") (pin "2") (pinfunction "Aout_2") (pintype "passive+no_connect"))
    )
    (net (code "85") (name "unconnected-(J3-D+-Pad3)") (class "Default")
      (node (ref "J3") (pin "3") (pinfunction "D+_3") (pintype "passive+no_connect"))
    )
    (net (code "86") (name "unconnected-(J3-D--Pad2)") (class "Default")
      (node (ref "J3") (pin "2") (pinfunction "D-_2") (pintype "passive+no_connect"))
    )
    (net (code "87") (name "unconnected-(J3-ID-Pad4)") (class "Default")
      (node (ref "J3") (pin "4") (pinfunction "ID_4") (pintype "passive+no_connect"))
    )
    (net (code "88") (name "unconnected-(J3-PadMP1)") (class "Default")
      (node (ref "J3") (pin "MP1") (pinfunction "MP1_MP1") (pintype "passive+no_connect"))
    )
    (net (code "89") (name "unconnected-(J3-PadMP2)") (class "Default")
      (node (ref "J3") (pin "MP2") (pinfunction "MP2_MP2") (pintype "passive+no_connect"))
    )
    (net (code "90") (name "unconnected-(J3-PadMP3)") (class "Default")
      (node (ref "J3") (pin "MP3") (pinfunction "MP3_MP3") (pintype "passive+no_connect"))
    )
    (net (code "91") (name "unconnected-(J3-PadMP4)") (class "Default")
      (node (ref "J3") (pin "MP4") (pinfunction "MP4_MP4") (pintype "passive+no_connect"))
    )
    (net (code "92") (name "unconnected-(J3-PadMP5)") (class "Default")
      (node (ref "J3") (pin "MP5") (pinfunction "MP5_MP5") (pintype "passive+no_connect"))
    )
    (net (code "93") (name "unconnected-(J3-PadMP6)") (class "Default")
      (node (ref "J3") (pin "MP6") (pinfunction "MP6_MP6") (pintype "passive+no_connect"))
    )
    (net (code "94") (name "unconnected-(PS1-NC-Pad4)") (class "Default")
      (node (ref "PS1") (pin "4") (pinfunction "NC_4") (pintype "passive+no_connect"))
    )
    (net (code "95") (name "unconnected-(RFID1-IRG-Pad5)") (class "Default")
      (node (ref "RFID1") (pin "5") (pinfunction "IRG_5") (pintype "output+no_connect"))
    )
    (net (code "96") (name "unconnected-(U2-CLK-Pad38)") (class "Default")
      (node (ref "U2") (pin "38") (pinfunction "CLK_38") (pintype "input+no_connect"))
    )
    (net (code "97") (name "unconnected-(U2-EN-Pad2)") (class "Default")
      (node (ref "U2") (pin "2") (pinfunction "EN_2") (pintype "input+no_connect"))
    )
    (net (code "98") (name "unconnected-(U2-EXT_5V-Pad19)") (class "Default")
      (node (ref "U2") (pin "19") (pinfunction "EXT_5V_19") (pintype "power_in"))
    )
    (net (code "99") (name "unconnected-(U2-SD0-Pad37)") (class "Default")
      (node (ref "U2") (pin "37") (pinfunction "SD0_37") (pintype "bidirectional+no_connect"))
    )
    (net (code "100") (name "unconnected-(U2-SD1-Pad36)") (class "Default")
      (node (ref "U2") (pin "36") (pinfunction "SD1_36") (pintype "bidirectional+no_connect"))
    )
    (net (code "101") (name "unconnected-(U2-SENSOR_VN-Pad4)") (class "Default")
      (node (ref "U2") (pin "4") (pinfunction "SENSOR_VN_4") (pintype "input+no_connect"))
    )
    (net (code "102") (name "unconnected-(U2-SENSOR_VP-Pad3)") (class "Default")
      (node (ref "U2") (pin "3") (pinfunction "SENSOR_VP_3") (pintype "input+no_connect"))
    )
    (net (code "103") (name "unconnected-(U8-TD-Pad4)") (class "Default")
      (node (ref "U8") (pin "4") (pinfunction "TD_4") (pintype "bidirectional+no_connect"))
    )
  )
)
